# Sheet4.net
KiCad netlist of a schematic drawn in Altium Designer
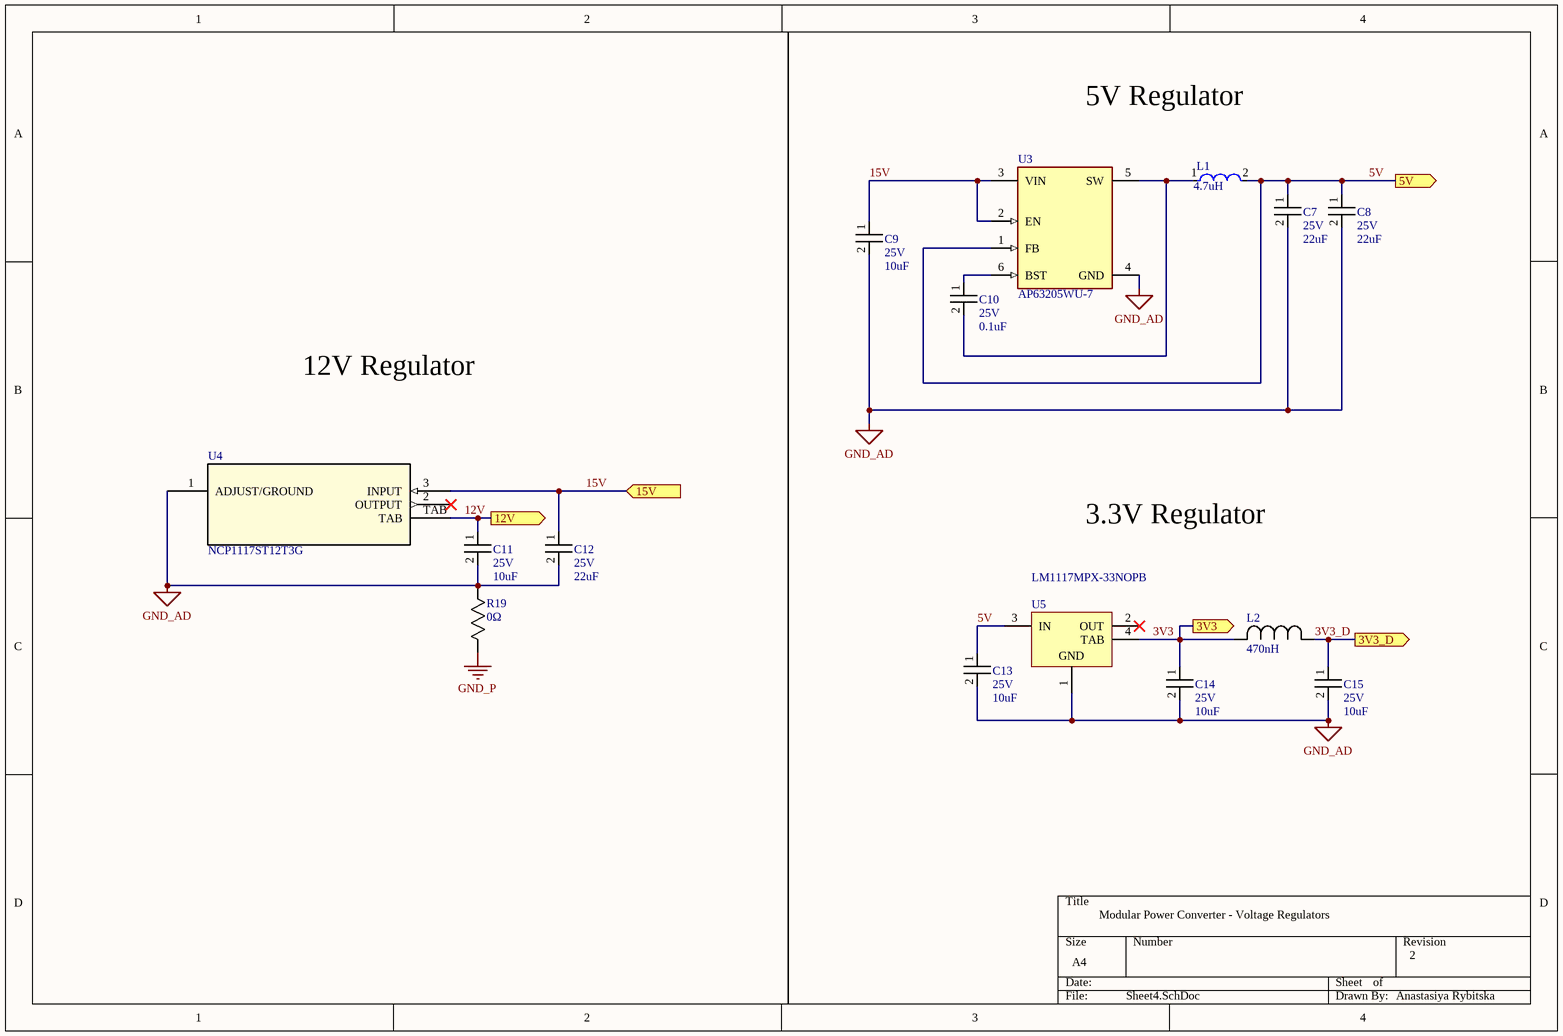
[diagram p0: Sheet4.SchDoc]

(export (version "E")
  (design (tool "Eeschema 10.0.6"))
  (components
    (comp (ref "C7")
      (value "CL21A226MAYNNNE")
      (footprint "0805")
      (description "22 µF ±20% 25V Ceramic Capacitor X5R 0805 (2012 Metric)")
      (fields (field (name "VOLTAGE RATING") "25V") (field (name "CAPACITANCE") "22uF"))
      (libsource (lib "Schlib1") (part "TMK212BBJ106KG-T"))
    )
    (comp (ref "C8")
      (value "CL21A226MAYNNNE")
      (footprint "0805")
      (description "22 µF ±20% 25V Ceramic Capacitor X5R 0805 (2012 Metric)")
      (fields (field (name "VOLTAGE RATING") "25V") (field (name "CAPACITANCE") "22uF"))
      (libsource (lib "Schlib1") (part "TMK212BBJ106KG-T"))
    )
    (comp (ref "C9")
      (value "TMK212BBJ106KG-T")
      (footprint "0805")
      (description "Multilayer Ceramic Capacitor 10uF 25V X5R 10% SMD 0805 T/R")
      (fields (field (name "VOLTAGE RATING") "25V") (field (name "CAPACITANCE") "10uF"))
      (libsource (lib "Schlib1") (part "TMK212BBJ106KG-T"))
    )
    (comp (ref "C10")
      (value "CC0603MRX7R8BB104")
      (footprint "0603")
      (description "CAP CER 0.1UF 25V X7R 0603")
      (fields (field (name "VOLTAGE RATING") "25V") (field (name "CAPACITANCE") "0.1uF"))
      (libsource (lib "Schlib1") (part "CC0603MRX7R8BB104"))
    )
    (comp (ref "C11")
      (value "TMK212BBJ106KG-T")
      (footprint "0805")
      (description "Multilayer Ceramic Capacitor 10uF 25V X5R 10% SMD 0805 T/R")
      (fields (field (name "VOLTAGE RATING") "25V") (field (name "CAPACITANCE") "10uF"))
      (libsource (lib "Schlib1") (part "TMK212BBJ106KG-T"))
    )
    (comp (ref "C12")
      (value "CL21A226MAYNNNE")
      (footprint "0805")
      (description "22 µF ±20% 25V Ceramic Capacitor X5R 0805 (2012 Metric)")
      (fields (field (name "VOLTAGE RATING") "25V") (field (name "CAPACITANCE") "22uF"))
      (libsource (lib "Schlib1") (part "TMK212BBJ106KG-T"))
    )
    (comp (ref "C13")
      (value "TMK212BBJ106KG-T")
      (footprint "0805")
      (description "Multilayer Ceramic Capacitor 10uF 25V X5R 10% SMD 0805 T/R")
      (fields (field (name "VOLTAGE RATING") "25V") (field (name "CAPACITANCE") "10uF"))
      (libsource (lib "Schlib1") (part "TMK212BBJ106KG-T"))
    )
    (comp (ref "C14")
      (value "TMK212BBJ106KG-T")
      (footprint "0805")
      (description "Multilayer Ceramic Capacitor 10uF 25V X5R 10% SMD 0805 T/R")
      (fields (field (name "VOLTAGE RATING") "25V") (field (name "CAPACITANCE") "10uF"))
      (libsource (lib "Schlib1") (part "TMK212BBJ106KG-T"))
    )
    (comp (ref "C15")
      (value "TMK212BBJ106KG-T")
      (footprint "0805")
      (description "Multilayer Ceramic Capacitor 10uF 25V X5R 10% SMD 0805 T/R")
      (fields (field (name "VOLTAGE RATING") "25V") (field (name "CAPACITANCE") "10uF"))
      (libsource (lib "Schlib1") (part "TMK212BBJ106KG-T"))
    )
    (comp (ref "L1")
      (value "MLZ2012M4R7WT000")
      (footprint "FP-MLZ2012-0_85-IPC_B")
      (description "Shielded Multilayer Inductor 4.7uH ±20% 500mA 390mΩ SMD 0805")
      (fields (field (name "INDUCTANCE") "4.7uH") (field (name "TOLERANCE") "20%"))
      (libsource (lib "Altium Content Vault") (part "725321dda6339637d4d059423bc1c3c"))
    )
    (comp (ref "L2")
      (value "MLZ2012DR47DT000")
      (footprint "0805")
      (description "Shielded Multilayer Inductor 470nH ±20% 700mA 234mΩ SMD 0805")
      (fields (field (name "INDUCTANCE") "470nH"))
      (libsource (lib "Schlib1") (part "MLZ2012DR47DT000"))
    )
    (comp (ref "R19")
      (value "AC0603FR-070RL")
      (footprint "0603")
      (description "RES SMD 0 OHM JUMPER 1/10W 0603")
      (fields (field (name "RESISTANCE") "0Ω"))
      (libsource (lib "Schlib1") (part "AC0603FR-070RL"))
    )
    (comp (ref "U3")
      (value "AP63205WU-7")
      (footprint "FP-TSOT26-MFG")
      (description "IC REG BUCK 5V 2A TSOT26")
      (fields
        (field (name "MANUFACTURER") "Diodes Inc.")
        (field (name "OCTOPART") "https://octopart.com/ap63205wu-7-diodes+inc.-98099551")
      )
      (libsource (lib "Altium Content Vault") (part "029bc9fbfa4a99dbb8b3a24c2adb655"))
    )
    (comp (ref "U4")
      (value "NCP1117ST12T3G")
      (footprint "SOT223-3_ONS")
      (description "No Description Available")
      (fields (field (name "COPYRIGHT") "Copyright (C) 2022 Ultra Librarian. All rights reserved."))
      (libsource (lib "NCP1117ST12T3G") (part "NCP1117ST12T3G"))
    )
    (comp (ref "U5")
      (value "LM1117MPX-33NOPB")
      (footprint "DCY0004A_L")
      (description "IC REG LINEAR 3.3V 800MA SOT223")
      (fields (field (name "MANUFACTURER") "onsemi"))
      (libsource (lib "Altium Content Vault") (part "PM-REG-LM1086-SOT4"))
    )
  )
  (nets
    (net (code "1") (name "/3V3") (class "Default")
      (node (ref "C14") (pin "1") (pinfunction "1_1") (pintype "passive"))
      (node (ref "L2") (pin "2") (pinfunction "2_2") (pintype "passive"))
      (node (ref "U5") (pin "4") (pinfunction "TAB_4") (pintype "passive"))
    )
    (net (code "2") (name "/3V3_D") (class "Default")
      (node (ref "C15") (pin "1") (pinfunction "1_1") (pintype "passive"))
      (node (ref "L2") (pin "1") (pinfunction "1_1") (pintype "passive"))
    )
    (net (code "3") (name "/5V") (class "Default")
      (node (ref "C13") (pin "1") (pinfunction "1_1") (pintype "passive"))
      (node (ref "C7") (pin "1") (pinfunction "1_1") (pintype "passive"))
      (node (ref "C8") (pin "1") (pinfunction "1_1") (pintype "passive"))
      (node (ref "L1") (pin "2") (pinfunction "2_2") (pintype "passive"))
      (node (ref "U3") (pin "1") (pinfunction "FB_1") (pintype "input"))
      (node (ref "U5") (pin "3") (pinfunction "IN_3") (pintype "passive"))
    )
    (net (code "4") (name "/12V") (class "Default")
      (node (ref "C11") (pin "1") (pinfunction "1_1") (pintype "passive"))
      (node (ref "U4") (pin "TAB") (pinfunction "TAB_TAB") (pintype "passive"))
    )
    (net (code "5") (name "/15V") (class "Default")
      (node (ref "C12") (pin "1") (pinfunction "1_1") (pintype "passive"))
      (node (ref "C9") (pin "1") (pinfunction "1_1") (pintype "passive"))
      (node (ref "U3") (pin "2") (pinfunction "EN_2") (pintype "input"))
      (node (ref "U3") (pin "3") (pinfunction "VIN_3") (pintype "passive"))
      (node (ref "U4") (pin "3") (pinfunction "INPUT_3") (pintype "input"))
    )
    (net (code "6") (name "GND_AD") (class "Default")
      (node (ref "C11") (pin "2") (pinfunction "2_2") (pintype "passive"))
      (node (ref "C12") (pin "2") (pinfunction "2_2") (pintype "passive"))
      (node (ref "C13") (pin "2") (pinfunction "2_2") (pintype "passive"))
      (node (ref "C14") (pin "2") (pinfunction "2_2") (pintype "passive"))
      (node (ref "C15") (pin "2") (pinfunction "2_2") (pintype "passive"))
      (node (ref "C7") (pin "2") (pinfunction "2_2") (pintype "passive"))
      (node (ref "C8") (pin "2") (pinfunction "2_2") (pintype "passive"))
      (node (ref "C9") (pin "2") (pinfunction "2_2") (pintype "passive"))
      (node (ref "R19") (pin "1") (pinfunction "1_1") (pintype "passive"))
      (node (ref "U3") (pin "4") (pinfunction "GND_4") (pintype "power_in"))
      (node (ref "U4") (pin "1") (pinfunction "ADJUST/GROUND_1") (pintype "passive"))
      (node (ref "U5") (pin "1") (pinfunction "GND_1") (pintype "power_in"))
    )
    (net (code "7") (name "GND_P") (class "Default")
      (node (ref "R19") (pin "2") (pinfunction "2_2") (pintype "passive"))
    )
    (net (code "8") (name "Net-(U3-BST)") (class "Default")
      (node (ref "C10") (pin "1") (pinfunction "1_1") (pintype "passive"))
      (node (ref "U3") (pin "6") (pinfunction "BST_6") (pintype "input"))
    )
    (net (code "9") (name "Net-(U3-SW)") (class "Default")
      (node (ref "C10") (pin "2") (pinfunction "2_2") (pintype "passive"))
      (node (ref "L1") (pin "1") (pinfunction "1_1") (pintype "passive"))
      (node (ref "U3") (pin "5") (pinfunction "SW_5") (pintype "power_in"))
    )
    (net (code "10") (name "unconnected-(U4-OUTPUT-Pad2)") (class "Default")
      (node (ref "U4") (pin "2") (pinfunction "OUTPUT_2") (pintype "output+no_connect"))
    )
    (net (code "11") (name "unconnected-(U5-OUT-Pad2)") (class "Default")
      (node (ref "U5") (pin "2") (pinfunction "OUT_2") (pintype "power_in+no_connect"))
    )
  )
)
